# FqMeterBF.net
KiCad netlist of a schematic drawn in EAGLE
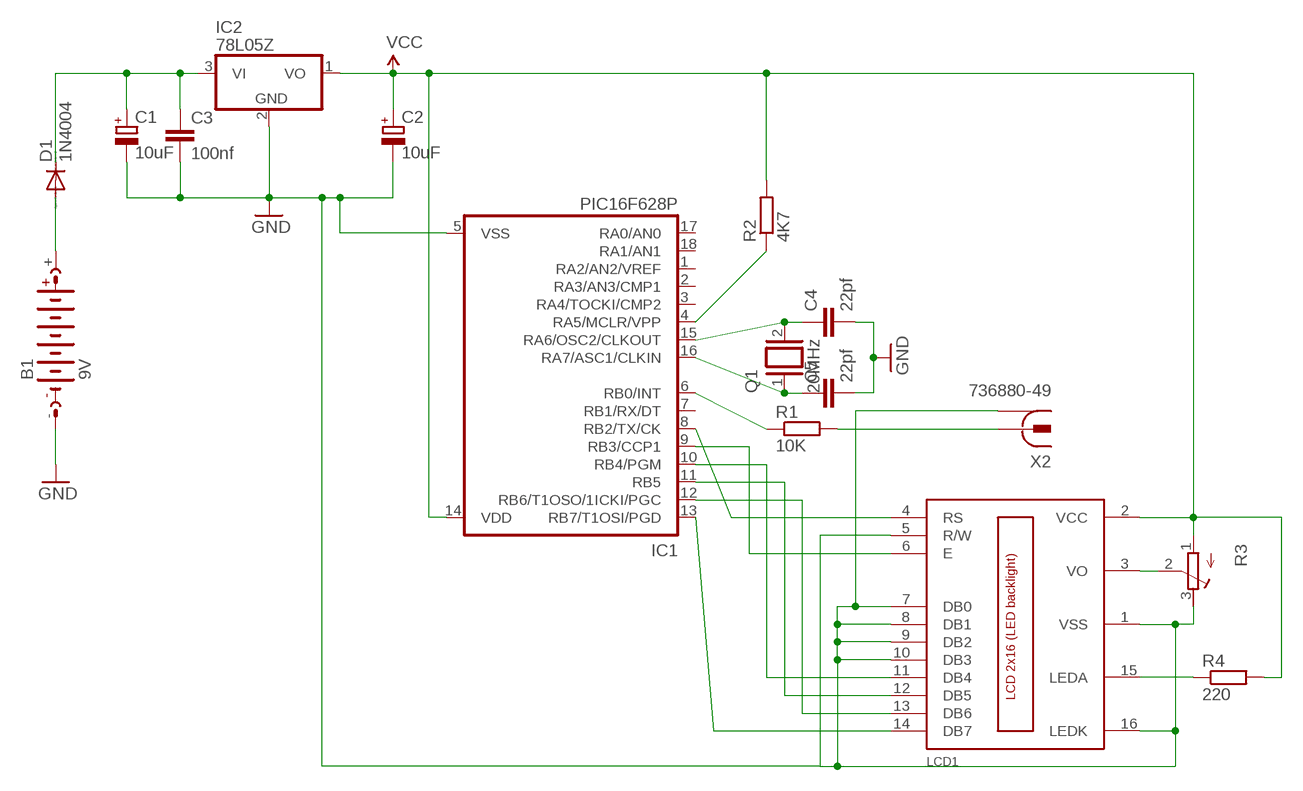
[diagram p0: schematic, sheet 1]

(export (version "E")
  (design (tool "Eeschema 10.0.6"))
  (components
    (comp (ref "B1")
      (value "9V")
      (footprint "eagle-import:AB9V")
      (libsource (lib "eagle-import") (part "AB9V"))
    )
    (comp (ref "C1")
      (value "10uF")
      (footprint "eagle-import:E2-4")
      (libsource (lib "eagle-import") (part "CPOL-EUE2-4"))
    )
    (comp (ref "C2")
      (value "10uF")
      (footprint "eagle-import:E2-4")
      (libsource (lib "eagle-import") (part "CPOL-EUE2-4"))
    )
    (comp (ref "C3")
      (value "100nf")
      (footprint "eagle-import:C050-025X075")
      (libsource (lib "eagle-import") (part "C-EU050-025X075"))
    )
    (comp (ref "C4")
      (value "22pf")
      (footprint "eagle-import:C050-025X075")
      (libsource (lib "eagle-import") (part "C-EU050-025X075"))
    )
    (comp (ref "C5")
      (value "22pf")
      (footprint "eagle-import:C050-025X075")
      (libsource (lib "eagle-import") (part "C-EU050-025X075"))
    )
    (comp (ref "D1")
      (value "1N4004")
      (footprint "eagle-import:DO41-10")
      (libsource (lib "eagle-import") (part "1N4004"))
    )
    (comp (ref "IC1")
      (value "PIC16F628P")
      (footprint "eagle-import:DIL18")
      (fields (field (name "MF") "MICROCHIP") (field (name "MPN") "PIC16F628-20/P"))
      (libsource (lib "eagle-import") (part "PIC16F628P"))
    )
    (comp (ref "IC2")
      (value "78L05Z")
      (footprint "eagle-import:TO92")
      (libsource (lib "eagle-import") (part "78ZL05"))
    )
    (comp (ref "LCD1")
      (value "LCD_2X16")
      (footprint "eagle-import:HY-1602F")
      (libsource (lib "eagle-import") (part "LCD_2X16"))
    )
    (comp (ref "Q1")
      (value "20MHz")
      (footprint "eagle-import:QS")
      (libsource (lib "eagle-import") (part "XTAL/S"))
    )
    (comp (ref "R1")
      (value "10K")
      (footprint "eagle-import:0207_12")
      (libsource (lib "eagle-import") (part "R-EU_0207/12"))
    )
    (comp (ref "R2")
      (value "4K7")
      (footprint "eagle-import:0207_12")
      (libsource (lib "eagle-import") (part "R-EU_0207/12"))
    )
    (comp (ref "R3")
      (value "R-TRIMM3339P")
      (footprint "eagle-import:RTRIM3339P")
      (libsource (lib "eagle-import") (part "R-TRIMM3339P"))
    )
    (comp (ref "R4")
      (value "220")
      (footprint "eagle-import:0207_12")
      (libsource (lib "eagle-import") (part "R-EU_0207/12"))
    )
    (comp (ref "X2")
      (value "736880-49")
      (footprint "eagle-import:736880-49")
      (libsource (lib "eagle-import") (part "736880-49"))
    )
  )
  (nets
    (net (code "1") (name "GND") (class "Default")
      (node (ref "B1") (pin "-") (pinfunction "-_-") (pintype "passive"))
      (node (ref "C1") (pin "-") (pinfunction "-_-") (pintype "passive"))
      (node (ref "C2") (pin "-") (pinfunction "-_-") (pintype "passive"))
      (node (ref "C3") (pin "2") (pinfunction "2_2") (pintype "passive"))
      (node (ref "C4") (pin "2") (pinfunction "2_2") (pintype "passive"))
      (node (ref "C5") (pin "2") (pinfunction "2_2") (pintype "passive"))
      (node (ref "IC1") (pin "5") (pinfunction "VSS_5") (pintype "power_in"))
      (node (ref "IC2") (pin "2") (pinfunction "GND_2") (pintype "passive"))
      (node (ref "LCD1") (pin "1") (pinfunction "VSS_1") (pintype "power_in"))
      (node (ref "LCD1") (pin "10") (pinfunction "DB3_10") (pintype "bidirectional"))
      (node (ref "LCD1") (pin "16") (pinfunction "LEDK_16") (pintype "passive"))
      (node (ref "LCD1") (pin "5") (pinfunction "R/W_5") (pintype "input"))
      (node (ref "LCD1") (pin "7") (pinfunction "DB0_7") (pintype "bidirectional"))
      (node (ref "LCD1") (pin "8") (pinfunction "DB1_8") (pintype "bidirectional"))
      (node (ref "LCD1") (pin "9") (pinfunction "DB2_9") (pintype "bidirectional"))
      (node (ref "R3") (pin "3") (pinfunction "E_3") (pintype "passive"))
      (node (ref "X2") (pin "1") (pinfunction "1_1") (pintype "passive"))
      (node (ref "X2") (pin "1@1") (pinfunction "1_1@1") (pintype "passive"))
      (node (ref "X2") (pin "1@2") (pinfunction "1_1@2") (pintype "passive"))
    )
    (net (code "2") (name "Net-(B1-Pad+)") (class "Default")
      (node (ref "B1") (pin "+") (pinfunction "+_+") (pintype "passive"))
      (node (ref "D1") (pin "A") (pinfunction "A_A") (pintype "passive"))
    )
    (net (code "3") (name "Net-(IC1-RA5{slash}MCLR{slash}VPP)") (class "Default")
      (node (ref "IC1") (pin "4") (pinfunction "RA5/MCLR/VPP_4") (pintype "input"))
      (node (ref "R2") (pin "1") (pinfunction "1_1") (pintype "passive"))
    )
    (net (code "4") (name "Net-(IC1-RA6{slash}OSC2{slash}CLKOUT)") (class "Default")
      (node (ref "C4") (pin "1") (pinfunction "1_1") (pintype "passive"))
      (node (ref "IC1") (pin "15") (pinfunction "RA6/OSC2/CLKOUT_15") (pintype "bidirectional"))
      (node (ref "Q1") (pin "2") (pinfunction "2_2") (pintype "passive"))
    )
    (net (code "5") (name "Net-(IC1-RA7{slash}ASC1{slash}CLKIN)") (class "Default")
      (node (ref "C5") (pin "1") (pinfunction "1_1") (pintype "passive"))
      (node (ref "IC1") (pin "16") (pinfunction "RA7/ASC1/CLKIN_16") (pintype "bidirectional"))
      (node (ref "Q1") (pin "1") (pinfunction "1_1") (pintype "passive"))
    )
    (net (code "6") (name "Net-(IC1-RB0{slash}INT)") (class "Default")
      (node (ref "IC1") (pin "6") (pinfunction "RB0/INT_6") (pintype "bidirectional"))
      (node (ref "R1") (pin "1") (pinfunction "1_1") (pintype "passive"))
    )
    (net (code "7") (name "Net-(IC1-RB2{slash}TX{slash}CK)") (class "Default")
      (node (ref "IC1") (pin "8") (pinfunction "RB2/TX/CK_8") (pintype "bidirectional"))
      (node (ref "LCD1") (pin "4") (pinfunction "RS_4") (pintype "input"))
    )
    (net (code "8") (name "Net-(IC1-RB3{slash}CCP1)") (class "Default")
      (node (ref "IC1") (pin "9") (pinfunction "RB3/CCP1_9") (pintype "bidirectional"))
      (node (ref "LCD1") (pin "6") (pinfunction "E_6") (pintype "input"))
    )
    (net (code "9") (name "Net-(IC1-RB4{slash}PGM)") (class "Default")
      (node (ref "IC1") (pin "10") (pinfunction "RB4/PGM_10") (pintype "bidirectional"))
      (node (ref "LCD1") (pin "11") (pinfunction "DB4_11") (pintype "bidirectional"))
    )
    (net (code "10") (name "Net-(IC1-RB5)") (class "Default")
      (node (ref "IC1") (pin "11") (pinfunction "RB5_11") (pintype "bidirectional"))
      (node (ref "LCD1") (pin "12") (pinfunction "DB5_12") (pintype "bidirectional"))
    )
    (net (code "11") (name "Net-(IC1-RB6{slash}T1OSO{slash}1ICKI{slash}PGC)") (class "Default")
      (node (ref "IC1") (pin "12") (pinfunction "RB6/T1OSO/1ICKI/PGC_12") (pintype "bidirectional"))
      (node (ref "LCD1") (pin "13") (pinfunction "DB6_13") (pintype "bidirectional"))
    )
    (net (code "12") (name "Net-(IC1-RB7{slash}T1OSI{slash}PGD)") (class "Default")
      (node (ref "IC1") (pin "13") (pinfunction "RB7/T1OSI/PGD_13") (pintype "bidirectional"))
      (node (ref "LCD1") (pin "14") (pinfunction "DB7_14") (pintype "bidirectional"))
    )
    (net (code "13") (name "Net-(IC2-VI)") (class "Default")
      (node (ref "C1") (pin "+") (pinfunction "+_+") (pintype "passive"))
      (node (ref "C3") (pin "1") (pinfunction "1_1") (pintype "passive"))
      (node (ref "D1") (pin "C") (pinfunction "C_C") (pintype "passive"))
      (node (ref "IC2") (pin "3") (pinfunction "VI_3") (pintype "input"))
    )
    (net (code "14") (name "Net-(LCD1-LEDA)") (class "Default")
      (node (ref "LCD1") (pin "15") (pinfunction "LEDA_15") (pintype "passive"))
      (node (ref "R4") (pin "1") (pinfunction "1_1") (pintype "passive"))
    )
    (net (code "15") (name "Net-(LCD1-VO)") (class "Default")
      (node (ref "LCD1") (pin "3") (pinfunction "VO_3") (pintype "input"))
      (node (ref "R3") (pin "2") (pinfunction "S_2") (pintype "passive"))
    )
    (net (code "16") (name "Net-(R1-Pad2)") (class "Default")
      (node (ref "R1") (pin "2") (pinfunction "2_2") (pintype "passive"))
      (node (ref "X2") (pin "2") (pinfunction "2_2") (pintype "passive"))
    )
    (net (code "17") (name "VCC") (class "Default")
      (node (ref "C2") (pin "+") (pinfunction "+_+") (pintype "passive"))
      (node (ref "IC1") (pin "14") (pinfunction "VDD_14") (pintype "power_in"))
      (node (ref "IC2") (pin "1") (pinfunction "VO_1") (pintype "passive"))
      (node (ref "LCD1") (pin "2") (pinfunction "VCC_2") (pintype "power_in"))
      (node (ref "R2") (pin "2") (pinfunction "2_2") (pintype "passive"))
      (node (ref "R3") (pin "1") (pinfunction "A_1") (pintype "passive"))
      (node (ref "R4") (pin "2") (pinfunction "2_2") (pintype "passive"))
    )
    (net (code "18") (name "unconnected-(IC1-RA0{slash}AN0-Pad17)") (class "Default")
      (node (ref "IC1") (pin "17") (pinfunction "RA0/AN0_17") (pintype "bidirectional"))
    )
    (net (code "19") (name "unconnected-(IC1-RA1{slash}AN1-Pad18)") (class "Default")
      (node (ref "IC1") (pin "18") (pinfunction "RA1/AN1_18") (pintype "bidirectional"))
    )
    (net (code "20") (name "unconnected-(IC1-RA2{slash}AN2{slash}VREF-Pad1)") (class "Default")
      (node (ref "IC1") (pin "1") (pinfunction "RA2/AN2/VREF_1") (pintype "bidirectional"))
    )
    (net (code "21") (name "unconnected-(IC1-RA3{slash}AN3{slash}CMP1-Pad2)") (class "Default")
      (node (ref "IC1") (pin "2") (pinfunction "RA3/AN3/CMP1_2") (pintype "bidirectional"))
    )
    (net (code "22") (name "unconnected-(IC1-RA4{slash}TOCKI{slash}CMP2-Pad3)") (class "Default")
      (node (ref "IC1") (pin "3") (pinfunction "RA4/TOCKI/CMP2_3") (pintype "bidirectional"))
    )
    (net (code "23") (name "unconnected-(IC1-RB1{slash}RX{slash}DT-Pad7)") (class "Default")
      (node (ref "IC1") (pin "7") (pinfunction "RB1/RX/DT_7") (pintype "bidirectional"))
    )
  )
)
